# gatedelay_11-30-19.net
KiCad netlist of a schematic drawn in EAGLE
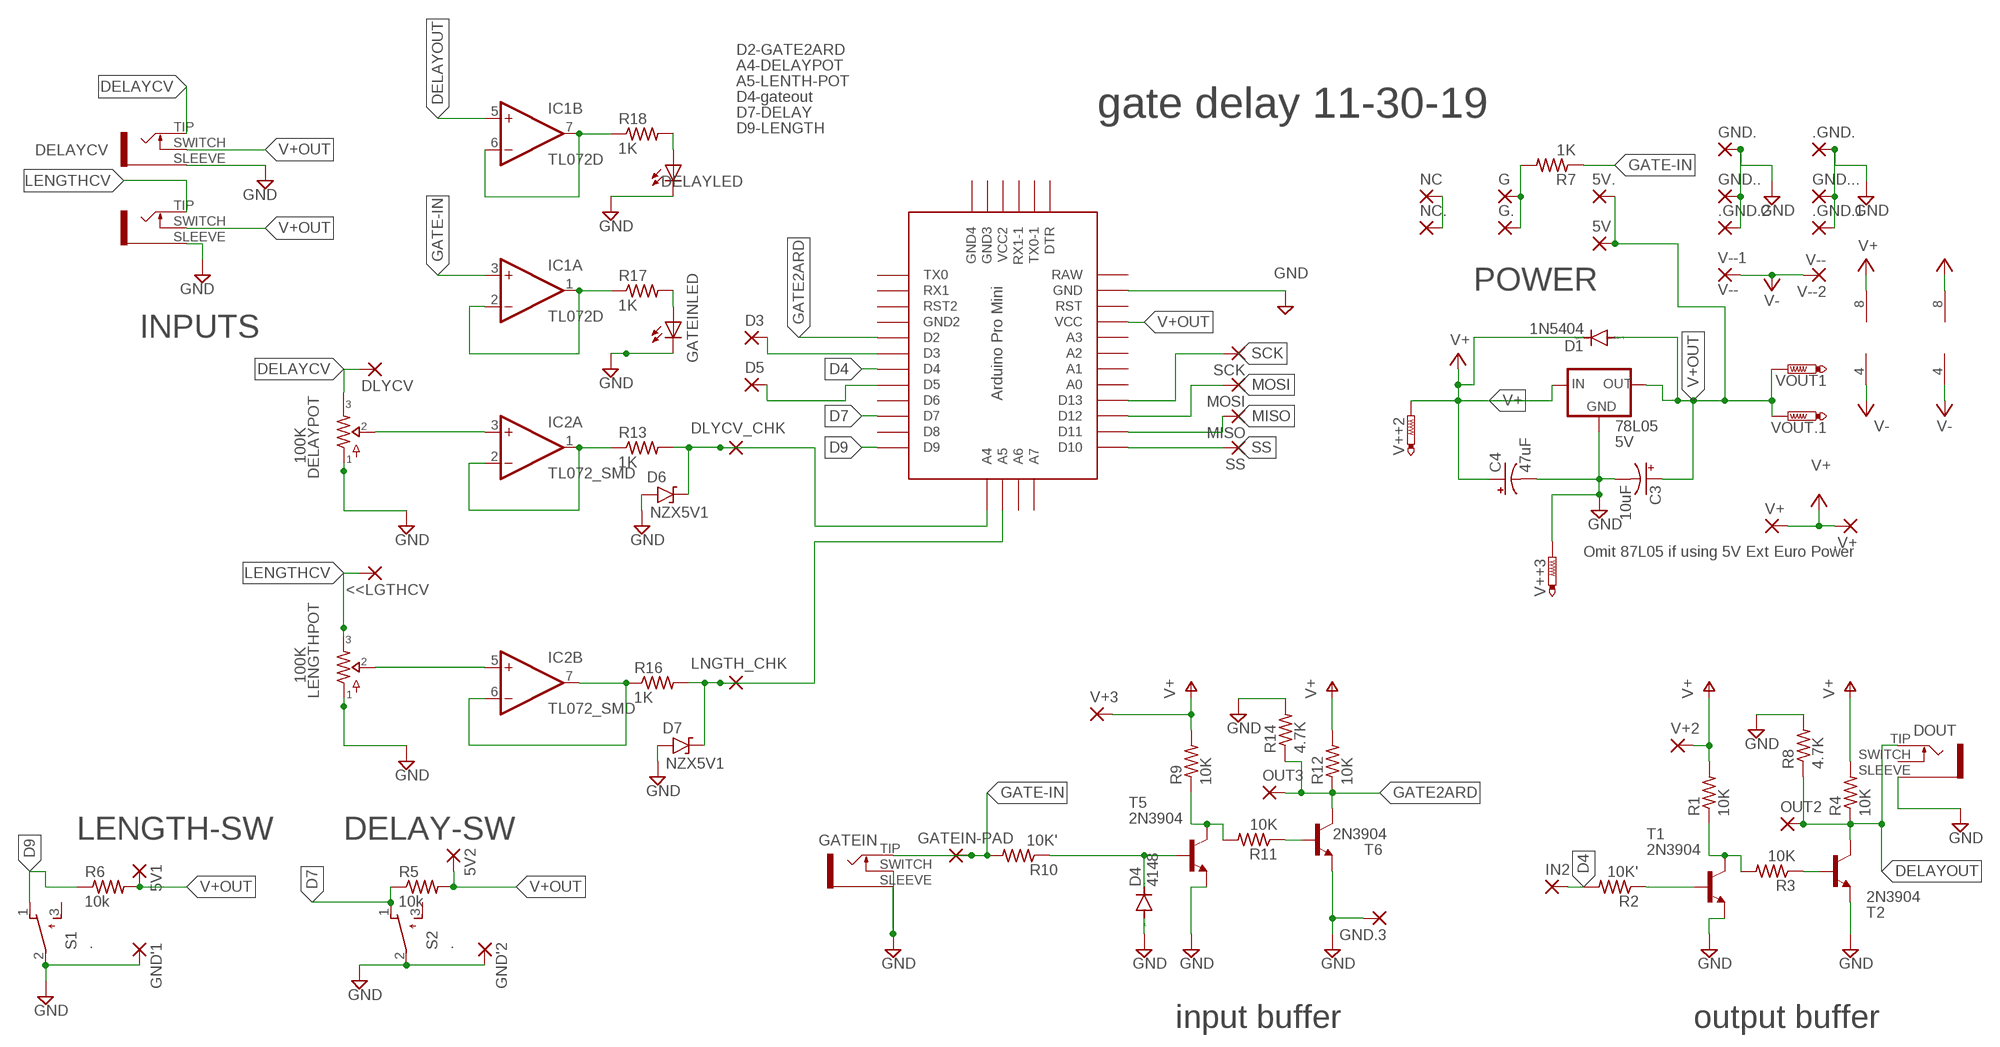
[diagram p0: schematic, sheet 1]

(export (version "E")
  (design (tool "Eeschema 10.0.6"))
  (components
    (comp (ref ".GND.")
      (value "1,6/0,8")
      (footprint "eagle-import:1,6_0,8")
      (libsource (lib "eagle-import") (part "1,6/0,8"))
    )
    (comp (ref ".GND.1")
      (value "1,6/0,8")
      (footprint "eagle-import:1,6_0,8")
      (libsource (lib "eagle-import") (part "1,6/0,8"))
    )
    (comp (ref ".GND.2")
      (value "1,6/0,8")
      (footprint "eagle-import:1,6_0,8")
      (libsource (lib "eagle-import") (part "1,6/0,8"))
    )
    (comp (ref ".V+")
      (value "1,6/0,8")
      (footprint "eagle-import:1,6_0,8")
      (libsource (lib "eagle-import") (part "1,6/0,8"))
    )
    (comp (ref "5V")
      (value "1,6/0,8")
      (footprint "eagle-import:1,6_0,8")
      (libsource (lib "eagle-import") (part "1,6/0,8"))
    )
    (comp (ref "5V.")
      (value "1,6/0,8")
      (footprint "eagle-import:1,6_0,8")
      (libsource (lib "eagle-import") (part "1,6/0,8"))
    )
    (comp (ref "5V1")
      (value "WIREPAD2,54/0,9")
      (footprint "eagle-import:2,54_0,9")
      (libsource (lib "eagle-import") (part "wirepad_412_WIREPAD2,54/0,9"))
    )
    (comp (ref "5V2")
      (value "WIREPAD2,54/0,9")
      (footprint "eagle-import:2,54_0,9")
      (libsource (lib "eagle-import") (part "wirepad_412_WIREPAD2,54/0,9"))
    )
    (comp (ref "78L05")
      (value "5V")
      (footprint "eagle-import:78LXX")
      (libsource (lib "eagle-import") (part "78LXX"))
    )
    (comp (ref "<<LGTHCV")
      (value "3,17/1,3")
      (footprint "eagle-import:3,17_1,3")
      (libsource (lib "eagle-import") (part "3,17/1,3"))
    )
    (comp (ref "C3")
      (value "10uF")
      (footprint "eagle-import:E2,5-6")
      (libsource (lib "eagle-import") (part "CPOL-USE2.5-6"))
    )
    (comp (ref "C4")
      (value "47uF")
      (footprint "eagle-import:E2,5-7")
      (libsource (lib "eagle-import") (part "CPOL-USE2.5-7"))
    )
    (comp (ref "D1")
      (value "1N5404")
      (footprint "eagle-import:DO35-10")
      (libsource (lib "eagle-import") (part "1N4148DO35-10"))
    )
    (comp (ref "D3")
      (value "WIREPAD2,15/1,0")
      (footprint "eagle-import:2,15_1,0")
      (libsource (lib "eagle-import") (part "wirepad_412_WIREPAD2,15/1,0"))
    )
    (comp (ref "D4")
      (value "4148")
      (footprint "eagle-import:DO35-7")
      (libsource (lib "eagle-import") (part "1N4148DO35-7"))
    )
    (comp (ref "D5")
      (value "WIREPAD2,15/1,0")
      (footprint "eagle-import:2,15_1,0")
      (libsource (lib "eagle-import") (part "wirepad_412_WIREPAD2,15/1,0"))
    )
    (comp (ref "D6")
      (value "NZX5V1")
      (footprint "eagle-import:DO41-2")
      (libsource (lib "eagle-import") (part "ZENER.2"))
    )
    (comp (ref "D7")
      (value "NZX5V1")
      (footprint "eagle-import:DO41-2")
      (libsource (lib "eagle-import") (part "ZENER.2"))
    )
    (comp (ref "DELAYCV")
      (value "35RAPC2AV")
      (footprint "eagle-import:35RAPCVAV")
      (libsource (lib "eagle-import") (part "35RAPC2AV"))
    )
    (comp (ref "DELAYLED")
      (value "LED3MM")
      (footprint "eagle-import:LED3MM")
      (libsource (lib "eagle-import") (part "LED3MM"))
    )
    (comp (ref "DELAYPOT")
      (value "100K")
      (footprint "eagle-import:9MM_VERT")
      (libsource (lib "eagle-import") (part "POTS9MM_VERT"))
    )
    (comp (ref "DLYCV")
      (value "WIREPAD1,6/0,9")
      (footprint "eagle-import:1,6_0,9")
      (libsource (lib "eagle-import") (part "WIREPAD1,6/0,9"))
    )
    (comp (ref "DLYCV_CHK")
      (value "3,17/1,3")
      (footprint "eagle-import:3,17_1,3")
      (libsource (lib "eagle-import") (part "3,17/1,3"))
    )
    (comp (ref "DOUT")
      (value "35RAPC2AV")
      (footprint "eagle-import:35RAPCVAV")
      (libsource (lib "eagle-import") (part "35RAPC2AV"))
    )
    (comp (ref "G")
      (value "1,6/0,8")
      (footprint "eagle-import:1,6_0,8")
      (libsource (lib "eagle-import") (part "1,6/0,8"))
    )
    (comp (ref "G.")
      (value "1,6/0,8")
      (footprint "eagle-import:1,6_0,8")
      (libsource (lib "eagle-import") (part "1,6/0,8"))
    )
    (comp (ref "GATEIN")
      (value "35RAPC2AV")
      (footprint "eagle-import:35RAPCVAV")
      (libsource (lib "eagle-import") (part "35RAPC2AV"))
    )
    (comp (ref "GATEIN-PAD")
      (value "WIREPAD1,6/0,9")
      (footprint "eagle-import:1,6_0,9")
      (libsource (lib "eagle-import") (part "WIREPAD1,6/0,9"))
    )
    (comp (ref "GATEINLED")
      (value "LED3MM")
      (footprint "eagle-import:LED3MM")
      (libsource (lib "eagle-import") (part "LED3MM"))
    )
    (comp (ref "GND'1")
      (value "WIREPAD2,54/0,9")
      (footprint "eagle-import:2,54_0,9")
      (libsource (lib "eagle-import") (part "wirepad_412_WIREPAD2,54/0,9"))
    )
    (comp (ref "GND'2")
      (value "WIREPAD2,54/0,9")
      (footprint "eagle-import:2,54_0,9")
      (libsource (lib "eagle-import") (part "wirepad_412_WIREPAD2,54/0,9"))
    )
    (comp (ref "GND.")
      (value "1,6/0,8")
      (footprint "eagle-import:1,6_0,8")
      (libsource (lib "eagle-import") (part "1,6/0,8"))
    )
    (comp (ref "GND..")
      (value "1,6/0,8")
      (footprint "eagle-import:1,6_0,8")
      (libsource (lib "eagle-import") (part "1,6/0,8"))
    )
    (comp (ref "GND...")
      (value "1,6/0,8")
      (footprint "eagle-import:1,6_0,8")
      (libsource (lib "eagle-import") (part "1,6/0,8"))
    )
    (comp (ref "GND.3")
      (value "WIREPAD1,6/0,9")
      (footprint "eagle-import:1,6_0,9")
      (libsource (lib "eagle-import") (part "WIREPAD1,6/0,9"))
    )
    (comp (ref "IC1")
      (value "TL072D")
      (footprint "eagle-import:SO08")
      (libsource (lib "eagle-import") (part "TL072D"))
    )
    (comp (ref "IC2")
      (value "TL072_SMD")
      (footprint "eagle-import:SO08")
      (libsource (lib "eagle-import") (part "TL072_SMD"))
    )
    (comp (ref "IN2")
      (value "WIREPAD1,6/0,9")
      (footprint "eagle-import:1,6_0,9")
      (libsource (lib "eagle-import") (part "WIREPAD1,6/0,9"))
    )
    (comp (ref "LENGTHCV")
      (value "35RAPC2AV")
      (footprint "eagle-import:35RAPCVAV")
      (libsource (lib "eagle-import") (part "35RAPC2AV"))
    )
    (comp (ref "LENGTHPOT")
      (value "100K")
      (footprint "eagle-import:9MM_VERT")
      (libsource (lib "eagle-import") (part "POTS9MM_VERT"))
    )
    (comp (ref "LNGTH_CHK")
      (value "3,17/1,3")
      (footprint "eagle-import:3,17_1,3")
      (libsource (lib "eagle-import") (part "3,17/1,3"))
    )
    (comp (ref "MISO")
      (value "WIREPAD1,6/0,9")
      (footprint "eagle-import:1,6_0,9")
      (libsource (lib "eagle-import") (part "WIREPAD1,6/0,9"))
    )
    (comp (ref "MOSI")
      (value "WIREPAD1,6/0,9")
      (footprint "eagle-import:1,6_0,9")
      (libsource (lib "eagle-import") (part "WIREPAD1,6/0,9"))
    )
    (comp (ref "NC")
      (value "1,6/0,8")
      (footprint "eagle-import:1,6_0,8")
      (libsource (lib "eagle-import") (part "1,6/0,8"))
    )
    (comp (ref "NC.")
      (value "1,6/0,8")
      (footprint "eagle-import:1,6_0,8")
      (libsource (lib "eagle-import") (part "1,6/0,8"))
    )
    (comp (ref "OUT2")
      (value "WIREPAD1,6/0,9")
      (footprint "eagle-import:1,6_0,9")
      (libsource (lib "eagle-import") (part "WIREPAD1,6/0,9"))
    )
    (comp (ref "OUT3")
      (value "WIREPAD1,6/0,9")
      (footprint "eagle-import:1,6_0,9")
      (libsource (lib "eagle-import") (part "WIREPAD1,6/0,9"))
    )
    (comp (ref "R1")
      (value "10K")
      (footprint "eagle-import:0204_5")
      (libsource (lib "eagle-import") (part "rcl_334_R-US_0204/5"))
    )
    (comp (ref "R2")
      (value "10K'")
      (footprint "eagle-import:0204_5")
      (libsource (lib "eagle-import") (part "rcl_334_R-US_0204/5"))
    )
    (comp (ref "R3")
      (value "10K")
      (footprint "eagle-import:0204_5")
      (libsource (lib "eagle-import") (part "rcl_334_R-US_0204/5"))
    )
    (comp (ref "R4")
      (value "10K")
      (footprint "eagle-import:0204_5")
      (libsource (lib "eagle-import") (part "rcl_334_R-US_0204/5"))
    )
    (comp (ref "R5")
      (value "10k")
      (footprint "eagle-import:0207_10")
      (libsource (lib "eagle-import") (part "R-US_0207/10"))
    )
    (comp (ref "R6")
      (value "10k")
      (footprint "eagle-import:0204_5")
      (libsource (lib "eagle-import") (part "R-US_0204/5"))
    )
    (comp (ref "R7")
      (value "1K")
      (footprint "eagle-import:0207_7")
      (libsource (lib "eagle-import") (part "R-US_0207/7"))
    )
    (comp (ref "R8")
      (value "4.7K")
      (footprint "eagle-import:0204_5")
      (libsource (lib "eagle-import") (part "rcl_334_R-US_0204/5"))
    )
    (comp (ref "R9")
      (value "10K")
      (footprint "eagle-import:0204_5")
      (libsource (lib "eagle-import") (part "rcl_334_R-US_0204/5"))
    )
    (comp (ref "R10")
      (value "10K'")
      (footprint "eagle-import:0204_5")
      (libsource (lib "eagle-import") (part "rcl_334_R-US_0204/5"))
    )
    (comp (ref "R11")
      (value "10K")
      (footprint "eagle-import:0204_5")
      (libsource (lib "eagle-import") (part "rcl_334_R-US_0204/5"))
    )
    (comp (ref "R12")
      (value "10K")
      (footprint "eagle-import:0204_5")
      (libsource (lib "eagle-import") (part "rcl_334_R-US_0204/5"))
    )
    (comp (ref "R13")
      (value "1K")
      (footprint "eagle-import:0204_7")
      (libsource (lib "eagle-import") (part "rcl_R-US_0204/7"))
    )
    (comp (ref "R14")
      (value "4.7K")
      (footprint "eagle-import:0204_5")
      (libsource (lib "eagle-import") (part "rcl_334_R-US_0204/5"))
    )
    (comp (ref "R16")
      (value "1K")
      (footprint "eagle-import:0204_7")
      (libsource (lib "eagle-import") (part "rcl_R-US_0204/7"))
    )
    (comp (ref "R17")
      (value "1K")
      (footprint "eagle-import:0204_7")
      (libsource (lib "eagle-import") (part "R-US_0204/7"))
    )
    (comp (ref "R18")
      (value "1K")
      (footprint "eagle-import:0207_15")
      (libsource (lib "eagle-import") (part "rcl_334_R-US_0207/15"))
    )
    (comp (ref "S1")
      (value ".")
      (footprint "eagle-import:ALCOSWTT11")
      (libsource (lib "eagle-import") (part "ALCOSWTT11"))
    )
    (comp (ref "S2")
      (value ".")
      (footprint "eagle-import:ALCOSWTT11")
      (libsource (lib "eagle-import") (part "ALCOSWTT11"))
    )
    (comp (ref "SCK")
      (value "WIREPAD1,6/0,9")
      (footprint "eagle-import:1,6_0,9")
      (libsource (lib "eagle-import") (part "WIREPAD1,6/0,9"))
    )
    (comp (ref "SS")
      (value "WIREPAD1,6/0,9")
      (footprint "eagle-import:1,6_0,9")
      (libsource (lib "eagle-import") (part "WIREPAD1,6/0,9"))
    )
    (comp (ref "T1")
      (value "2N3904")
      (footprint "eagle-import:TO92")
      (libsource (lib "eagle-import") (part "2N3904"))
    )
    (comp (ref "T2")
      (value "2N3904")
      (footprint "eagle-import:TO92")
      (libsource (lib "eagle-import") (part "2N3904"))
    )
    (comp (ref "T5")
      (value "2N3904")
      (footprint "eagle-import:TO92")
      (libsource (lib "eagle-import") (part "2N3904"))
    )
    (comp (ref "T6")
      (value "2N3904")
      (footprint "eagle-import:TO92")
      (libsource (lib "eagle-import") (part "2N3904"))
    )
    (comp (ref "U$1")
      (value "PRO-MINI")
      (footprint "eagle-import:PRO-MINI")
      (libsource (lib "eagle-import") (part "PRO-MINI"))
    )
    (comp (ref "V+")
      (value "1,6/0,8")
      (footprint "eagle-import:1,6_0,8")
      (libsource (lib "eagle-import") (part "1,6/0,8"))
    )
    (comp (ref "V++2")
      (value "PTR1PAD1-13Y")
      (footprint "eagle-import:P1-13Y")
      (libsource (lib "eagle-import") (part "PTR1PAD1-13Y"))
    )
    (comp (ref "V++3")
      (value "PTR1PAD1-13Y")
      (footprint "eagle-import:P1-13Y")
      (libsource (lib "eagle-import") (part "PTR1PAD1-13Y"))
    )
    (comp (ref "V+2")
      (value "WIREPAD1,6/0,9")
      (footprint "eagle-import:1,6_0,9")
      (libsource (lib "eagle-import") (part "WIREPAD1,6/0,9"))
    )
    (comp (ref "V+3")
      (value "WIREPAD1,6/0,9")
      (footprint "eagle-import:1,6_0,9")
      (libsource (lib "eagle-import") (part "WIREPAD1,6/0,9"))
    )
    (comp (ref "V--1")
      (value "V--")
      (footprint "eagle-import:1,6_0,8")
      (libsource (lib "eagle-import") (part "1,6/0,8"))
    )
    (comp (ref "V--2")
      (value "V--")
      (footprint "eagle-import:1,6_0,8")
      (libsource (lib "eagle-import") (part "1,6/0,8"))
    )
    (comp (ref "VOUT.1")
      (value "PTR1PAD1-13Y")
      (footprint "eagle-import:P1-13Y")
      (libsource (lib "eagle-import") (part "PTR1PAD1-13Y"))
    )
    (comp (ref "VOUT1")
      (value "PTR1PAD1-13Y")
      (footprint "eagle-import:P1-13Y")
      (libsource (lib "eagle-import") (part "PTR1PAD1-13Y"))
    )
  )
  (nets
    (net (code "1") (name "/RAW") (class "Default")
      (node (ref "U$1") (pin "RAW") (pinfunction "RAW_RAW") (pintype "power_in"))
    )
    (net (code "2") (name "D4") (class "Default")
      (node (ref "IN2") (pin "1") (pinfunction "P_1") (pintype "passive"))
      (node (ref "R2") (pin "2") (pinfunction "2_2") (pintype "passive"))
      (node (ref "U$1") (pin "D4") (pinfunction "D4_D4") (pintype "bidirectional"))
    )
    (net (code "3") (name "D7") (class "Default")
      (node (ref "R5") (pin "1") (pinfunction "1_1") (pintype "passive"))
      (node (ref "S2") (pin "1") (pinfunction "O_1") (pintype "passive"))
      (node (ref "U$1") (pin "D7") (pinfunction "D7_D7") (pintype "bidirectional"))
    )
    (net (code "4") (name "D9") (class "Default")
      (node (ref "R6") (pin "1") (pinfunction "1_1") (pintype "passive"))
      (node (ref "S1") (pin "1") (pinfunction "O_1") (pintype "passive"))
      (node (ref "U$1") (pin "D9") (pinfunction "D9_D9") (pintype "bidirectional"))
    )
    (net (code "5") (name "DELAYCV") (class "Default")
      (node (ref "DELAYCV") (pin "TIP") (pinfunction "2_TIP") (pintype "passive"))
      (node (ref "DELAYPOT") (pin "3") (pinfunction "3_3") (pintype "passive"))
      (node (ref "DLYCV") (pin "1") (pinfunction "P_1") (pintype "passive"))
    )
    (net (code "6") (name "DELAYOUT") (class "Default")
      (node (ref "DOUT") (pin "TIP") (pinfunction "2_TIP") (pintype "passive"))
      (node (ref "IC1") (pin "5") (pinfunction "+IN_5") (pintype "input"))
      (node (ref "OUT2") (pin "1") (pinfunction "P_1") (pintype "passive"))
      (node (ref "R4") (pin "1") (pinfunction "1_1") (pintype "passive"))
      (node (ref "R8") (pin "1") (pinfunction "1_1") (pintype "passive"))
      (node (ref "T2") (pin "1") (pinfunction "C_1") (pintype "passive"))
    )
    (net (code "7") (name "GATE-IN") (class "Default")
      (node (ref "GATEIN") (pin "TIP") (pinfunction "2_TIP") (pintype "passive"))
      (node (ref "GATEIN-PAD") (pin "1") (pinfunction "P_1") (pintype "passive"))
      (node (ref "IC1") (pin "3") (pinfunction "+IN_3") (pintype "input"))
      (node (ref "R10") (pin "2") (pinfunction "2_2") (pintype "passive"))
      (node (ref "R7") (pin "1") (pinfunction "1_1") (pintype "passive"))
    )
    (net (code "8") (name "GATE2ARD") (class "Default")
      (node (ref "OUT3") (pin "1") (pinfunction "P_1") (pintype "passive"))
      (node (ref "R12") (pin "1") (pinfunction "1_1") (pintype "passive"))
      (node (ref "R14") (pin "1") (pinfunction "1_1") (pintype "passive"))
      (node (ref "T6") (pin "1") (pinfunction "C_1") (pintype "passive"))
      (node (ref "U$1") (pin "D2") (pinfunction "D2_D2") (pintype "bidirectional"))
    )
    (net (code "9") (name "GND") (class "Default")
      (node (ref ".GND.") (pin "1") (pinfunction "P_1") (pintype "passive"))
      (node (ref ".GND.1") (pin "1") (pinfunction "P_1") (pintype "passive"))
      (node (ref ".GND.2") (pin "1") (pinfunction "P_1") (pintype "passive"))
      (node (ref "78L05") (pin "GND") (pinfunction "GND_GND") (pintype "input"))
      (node (ref "C3") (pin "-") (pinfunction "-_-") (pintype "passive"))
      (node (ref "C4") (pin "-") (pinfunction "-_-") (pintype "passive"))
      (node (ref "D4") (pin "A") (pinfunction "A_A") (pintype "passive"))
      (node (ref "D6") (pin "A") (pinfunction "A_A") (pintype "passive"))
      (node (ref "D7") (pin "A") (pinfunction "A_A") (pintype "passive"))
      (node (ref "DELAYCV") (pin "SLEEVE") (pinfunction "1_SLEEVE") (pintype "passive"))
      (node (ref "DELAYLED") (pin "K") (pinfunction "C_K") (pintype "passive"))
      (node (ref "DELAYPOT") (pin "1") (pinfunction "1_1") (pintype "passive"))
      (node (ref "DOUT") (pin "SLEEVE") (pinfunction "1_SLEEVE") (pintype "passive"))
      (node (ref "GATEIN") (pin "SLEEVE") (pinfunction "1_SLEEVE") (pintype "passive"))
      (node (ref "GATEIN") (pin "SWITCH") (pinfunction "3_SWITCH") (pintype "passive"))
      (node (ref "GATEINLED") (pin "K") (pinfunction "C_K") (pintype "passive"))
      (node (ref "GND'1") (pin "1") (pinfunction "P_1") (pintype "passive"))
      (node (ref "GND'2") (pin "1") (pinfunction "P_1") (pintype "passive"))
      (node (ref "GND.") (pin "1") (pinfunction "P_1") (pintype "passive"))
      (node (ref "GND..") (pin "1") (pinfunction "P_1") (pintype "passive"))
      (node (ref "GND...") (pin "1") (pinfunction "P_1") (pintype "passive"))
      (node (ref "GND.3") (pin "1") (pinfunction "P_1") (pintype "passive"))
      (node (ref "LENGTHCV") (pin "SLEEVE") (pinfunction "1_SLEEVE") (pintype "passive"))
      (node (ref "LENGTHPOT") (pin "1") (pinfunction "1_1") (pintype "passive"))
      (node (ref "R14") (pin "2") (pinfunction "2_2") (pintype "passive"))
      (node (ref "R8") (pin "2") (pinfunction "2_2") (pintype "passive"))
      (node (ref "S1") (pin "2") (pinfunction "P_2") (pintype "passive"))
      (node (ref "S2") (pin "2") (pinfunction "P_2") (pintype "passive"))
      (node (ref "T1") (pin "3") (pinfunction "E_3") (pintype "passive"))
      (node (ref "T2") (pin "3") (pinfunction "E_3") (pintype "passive"))
      (node (ref "T5") (pin "3") (pinfunction "E_3") (pintype "passive"))
      (node (ref "T6") (pin "3") (pinfunction "E_3") (pintype "passive"))
      (node (ref "U$1") (pin "GND") (pinfunction "GND_GND") (pintype "input"))
      (node (ref "V++3") (pin "TP") (pinfunction "TP_TP") (pintype "input"))
    )
    (net (code "10") (name "LENGTHCV") (class "Default")
      (node (ref "<<LGTHCV") (pin "1") (pinfunction "P_1") (pintype "passive"))
      (node (ref "LENGTHCV") (pin "TIP") (pinfunction "2_TIP") (pintype "passive"))
      (node (ref "LENGTHPOT") (pin "3") (pinfunction "3_3") (pintype "passive"))
    )
    (net (code "11") (name "MISO") (class "Default")
      (node (ref "MISO") (pin "1") (pinfunction "P_1") (pintype "passive"))
      (node (ref "U$1") (pin "D11") (pinfunction "D11_D11") (pintype "bidirectional"))
    )
    (net (code "12") (name "MOSI") (class "Default")
      (node (ref "MOSI") (pin "1") (pinfunction "P_1") (pintype "passive"))
      (node (ref "U$1") (pin "D12") (pinfunction "D12_D12") (pintype "bidirectional"))
    )
    (net (code "13") (name "Net-(D3-P)") (class "Default")
      (node (ref "D3") (pin "1") (pinfunction "P_1") (pintype "passive"))
      (node (ref "U$1") (pin "D3") (pinfunction "D3_D3") (pintype "bidirectional"))
    )
    (net (code "14") (name "Net-(D5-P)") (class "Default")
      (node (ref "D5") (pin "1") (pinfunction "P_1") (pintype "passive"))
      (node (ref "U$1") (pin "D5") (pinfunction "D5_D5") (pintype "bidirectional"))
    )
    (net (code "15") (name "Net-(DELAYLED-PadA)") (class "Default")
      (node (ref "DELAYLED") (pin "A") (pinfunction "A_A") (pintype "passive"))
      (node (ref "R18") (pin "2") (pinfunction "2_2") (pintype "passive"))
    )
    (net (code "16") (name "Net-(DLYCV_CHK-P)") (class "Default")
      (node (ref "D6") (pin "C") (pinfunction "C_C") (pintype "passive"))
      (node (ref "DLYCV_CHK") (pin "1") (pinfunction "P_1") (pintype "passive"))
      (node (ref "R13") (pin "2") (pinfunction "2_2") (pintype "passive"))
      (node (ref "U$1") (pin "A4") (pinfunction "A4_A4") (pintype "bidirectional"))
    )
    (net (code "17") (name "Net-(G-P)") (class "Default")
      (node (ref "G") (pin "1") (pinfunction "P_1") (pintype "passive"))
      (node (ref "G.") (pin "1") (pinfunction "P_1") (pintype "passive"))
      (node (ref "R7") (pin "2") (pinfunction "2_2") (pintype "passive"))
    )
    (net (code "18") (name "Net-(GATEINLED-PadA)") (class "Default")
      (node (ref "GATEINLED") (pin "A") (pinfunction "A_A") (pintype "passive"))
      (node (ref "R17") (pin "2") (pinfunction "2_2") (pintype "passive"))
    )
    (net (code "19") (name "Net-(IC1A--IN)") (class "Default")
      (node (ref "IC1") (pin "1") (pinfunction "OUT_1") (pintype "output"))
      (node (ref "IC1") (pin "2") (pinfunction "-IN_2") (pintype "input"))
      (node (ref "R17") (pin "1") (pinfunction "1_1") (pintype "passive"))
    )
    (net (code "20") (name "Net-(IC1B--IN)") (class "Default")
      (node (ref "IC1") (pin "6") (pinfunction "-IN_6") (pintype "input"))
      (node (ref "IC1") (pin "7") (pinfunction "OUT_7") (pintype "output"))
      (node (ref "R18") (pin "1") (pinfunction "1_1") (pintype "passive"))
    )
    (net (code "21") (name "Net-(IC2A-+IN)") (class "Default")
      (node (ref "DELAYPOT") (pin "2") (pinfunction "2_2") (pintype "passive"))
      (node (ref "IC2") (pin "3") (pinfunction "+IN_3") (pintype "input"))
    )
    (net (code "22") (name "Net-(IC2A--IN)") (class "Default")
      (node (ref "IC2") (pin "1") (pinfunction "OUT_1") (pintype "output"))
      (node (ref "IC2") (pin "2") (pinfunction "-IN_2") (pintype "input"))
      (node (ref "R13") (pin "1") (pinfunction "1_1") (pintype "passive"))
    )
    (net (code "23") (name "Net-(IC2B-+IN)") (class "Default")
      (node (ref "IC2") (pin "5") (pinfunction "+IN_5") (pintype "input"))
      (node (ref "LENGTHPOT") (pin "2") (pinfunction "2_2") (pintype "passive"))
    )
    (net (code "24") (name "Net-(IC2B--IN)") (class "Default")
      (node (ref "IC2") (pin "6") (pinfunction "-IN_6") (pintype "input"))
      (node (ref "IC2") (pin "7") (pinfunction "OUT_7") (pintype "output"))
      (node (ref "R16") (pin "1") (pinfunction "1_1") (pintype "passive"))
    )
    (net (code "25") (name "Net-(LNGTH_CHK-P)") (class "Default")
      (node (ref "D7") (pin "C") (pinfunction "C_C") (pintype "passive"))
      (node (ref "LNGTH_CHK") (pin "1") (pinfunction "P_1") (pintype "passive"))
      (node (ref "R16") (pin "2") (pinfunction "2_2") (pintype "passive"))
      (node (ref "U$1") (pin "A5") (pinfunction "A5_A5") (pintype "bidirectional"))
    )
    (net (code "26") (name "Net-(NC-P)") (class "Default")
      (node (ref "NC") (pin "1") (pinfunction "P_1") (pintype "passive"))
      (node (ref "NC.") (pin "1") (pinfunction "P_1") (pintype "passive"))
    )
    (net (code "27") (name "Net-(T1-B)") (class "Default")
      (node (ref "R2") (pin "1") (pinfunction "1_1") (pintype "passive"))
      (node (ref "T1") (pin "2") (pinfunction "B_2") (pintype "passive"))
    )
    (net (code "28") (name "Net-(T1-C)") (class "Default")
      (node (ref "R1") (pin "1") (pinfunction "1_1") (pintype "passive"))
      (node (ref "R3") (pin "2") (pinfunction "2_2") (pintype "passive"))
      (node (ref "T1") (pin "1") (pinfunction "C_1") (pintype "passive"))
    )
    (net (code "29") (name "Net-(T2-B)") (class "Default")
      (node (ref "R3") (pin "1") (pinfunction "1_1") (pintype "passive"))
      (node (ref "T2") (pin "2") (pinfunction "B_2") (pintype "passive"))
    )
    (net (code "30") (name "Net-(T5-B)") (class "Default")
      (node (ref "D4") (pin "C") (pinfunction "C_C") (pintype "passive"))
      (node (ref "R10") (pin "1") (pinfunction "1_1") (pintype "passive"))
      (node (ref "T5") (pin "2") (pinfunction "B_2") (pintype "passive"))
    )
    (net (code "31") (name "Net-(T5-C)") (class "Default")
      (node (ref "R11") (pin "2") (pinfunction "2_2") (pintype "passive"))
      (node (ref "R9") (pin "1") (pinfunction "1_1") (pintype "passive"))
      (node (ref "T5") (pin "1") (pinfunction "C_1") (pintype "passive"))
    )
    (net (code "32") (name "Net-(T6-B)") (class "Default")
      (node (ref "R11") (pin "1") (pinfunction "1_1") (pintype "passive"))
      (node (ref "T6") (pin "2") (pinfunction "B_2") (pintype "passive"))
    )
    (net (code "33") (name "SCK") (class "Default")
      (node (ref "SCK") (pin "1") (pinfunction "P_1") (pintype "passive"))
      (node (ref "U$1") (pin "D13") (pinfunction "D13_D13") (pintype "bidirectional"))
    )
    (net (code "34") (name "SS") (class "Default")
      (node (ref "SS") (pin "1") (pinfunction "P_1") (pintype "passive"))
      (node (ref "U$1") (pin "D10") (pinfunction "D10_D10") (pintype "bidirectional"))
    )
    (net (code "35") (name "V+") (class "Default")
      (node (ref ".V+") (pin "1") (pinfunction "P_1") (pintype "passive"))
      (node (ref "78L05") (pin "IN") (pinfunction "IN_IN") (pintype "input"))
      (node (ref "C4") (pin "+") (pinfunction "+_+") (pintype "passive"))
      (node (ref "D1") (pin "C") (pinfunction "C_C") (pintype "passive"))
      (node (ref "IC1") (pin "8") (pinfunction "V+_8") (pintype "power_in"))
      (node (ref "IC2") (pin "8") (pinfunction "V+_8") (pintype "power_in"))
      (node (ref "R1") (pin "2") (pinfunction "2_2") (pintype "passive"))
      (node (ref "R12") (pin "2") (pinfunction "2_2") (pintype "passive"))
      (node (ref "R4") (pin "2") (pinfunction "2_2") (pintype "passive"))
      (node (ref "R9") (pin "2") (pinfunction "2_2") (pintype "passive"))
      (node (ref "V+") (pin "1") (pinfunction "P_1") (pintype "passive"))
      (node (ref "V++2") (pin "TP") (pinfunction "TP_TP") (pintype "input"))
      (node (ref "V+2") (pin "1") (pinfunction "P_1") (pintype "passive"))
      (node (ref "V+3") (pin "1") (pinfunction "P_1") (pintype "passive"))
    )
    (net (code "36") (name "V+OUT") (class "Default")
      (node (ref "5V") (pin "1") (pinfunction "P_1") (pintype "passive"))
      (node (ref "5V.") (pin "1") (pinfunction "P_1") (pintype "passive"))
      (node (ref "5V1") (pin "1") (pinfunction "P_1") (pintype "passive"))
      (node (ref "5V2") (pin "1") (pinfunction "P_1") (pintype "passive"))
      (node (ref "78L05") (pin "OUT") (pinfunction "OUT_OUT") (pintype "passive"))
      (node (ref "C3") (pin "+") (pinfunction "+_+") (pintype "passive"))
      (node (ref "D1") (pin "A") (pinfunction "A_A") (pintype "passive"))
      (node (ref "DELAYCV") (pin "SWITCH") (pinfunction "3_SWITCH") (pintype "passive"))
      (node (ref "LENGTHCV") (pin "SWITCH") (pinfunction "3_SWITCH") (pintype "passive"))
      (node (ref "R5") (pin "2") (pinfunction "2_2") (pintype "passive"))
      (node (ref "R6") (pin "2") (pinfunction "2_2") (pintype "passive"))
      (node (ref "U$1") (pin "VCC") (pinfunction "VCC_VCC") (pintype "bidirectional"))
      (node (ref "VOUT.1") (pin "TP") (pinfunction "TP_TP") (pintype "input"))
      (node (ref "VOUT1") (pin "TP") (pinfunction "TP_TP") (pintype "input"))
    )
    (net (code "37") (name "V-") (class "Default")
      (node (ref "IC1") (pin "4") (pinfunction "V-_4") (pintype "power_in"))
      (node (ref "IC2") (pin "4") (pinfunction "V-_4") (pintype "power_in"))
      (node (ref "V--1") (pin "1") (pinfunction "P_1") (pintype "passive"))
      (node (ref "V--2") (pin "1") (pinfunction "P_1") (pintype "passive"))
    )
    (net (code "38") (name "unconnected-(DOUT-3-PadSWITCH)") (class "Default")
      (node (ref "DOUT") (pin "SWITCH") (pinfunction "3_SWITCH") (pintype "passive"))
    )
    (net (code "39") (name "unconnected-(S1-S-Pad3)") (class "Default")
      (node (ref "S1") (pin "3") (pinfunction "S_3") (pintype "passive"))
    )
    (net (code "40") (name "unconnected-(S2-S-Pad3)") (class "Default")
      (node (ref "S2") (pin "3") (pinfunction "S_3") (pintype "passive"))
    )
    (net (code "41") (name "unconnected-(U$1-GND2-PadGND1)") (class "Default")
      (node (ref "U$1") (pin "GND1") (pinfunction "GND2_GND1") (pintype "bidirectional"))
    )
    (net (code "42") (name "unconnected-(U$1-GND4-PadGND2)") (class "Default")
      (node (ref "U$1") (pin "GND2") (pinfunction "GND4_GND2") (pintype "bidirectional"))
    )
    (net (code "43") (name "unconnected-(U$1-PadA0)") (class "Default")
      (node (ref "U$1") (pin "A0") (pinfunction "A0_A0") (pintype "bidirectional"))
    )
    (net (code "44") (name "unconnected-(U$1-PadA1)") (class "Default")
      (node (ref "U$1") (pin "A1") (pinfunction "A1_A1") (pintype "bidirectional"))
    )
    (net (code "45") (name "unconnected-(U$1-PadA2)") (class "Default")
      (node (ref "U$1") (pin "A2") (pinfunction "A2_A2") (pintype "bidirectional"))
    )
    (net (code "46") (name "unconnected-(U$1-PadA3)") (class "Default")
      (node (ref "U$1") (pin "A3") (pinfunction "A3_A3") (pintype "bidirectional"))
    )
    (net (code "47") (name "unconnected-(U$1-PadA6)") (class "Default")
      (node (ref "U$1") (pin "A6") (pinfunction "A6_A6") (pintype "bidirectional"))
    )
    (net (code "48") (name "unconnected-(U$1-PadA7)") (class "Default")
      (node (ref "U$1") (pin "A7") (pinfunction "A7_A7") (pintype "bidirectional"))
    )
    (net (code "49") (name "unconnected-(U$1-PadD6)") (class "Default")
      (node (ref "U$1") (pin "D6") (pinfunction "D6_D6") (pintype "bidirectional"))
    )
    (net (code "50") (name "unconnected-(U$1-PadD8)") (class "Default")
      (node (ref "U$1") (pin "D8") (pinfunction "D8_D8") (pintype "bidirectional"))
    )
    (net (code "51") (name "unconnected-(U$1-PadDTR)") (class "Default")
      (node (ref "U$1") (pin "DTR") (pinfunction "DTR_DTR") (pintype "bidirectional"))
    )
    (net (code "52") (name "unconnected-(U$1-PadGND3)") (class "Default")
      (node (ref "U$1") (pin "GND3") (pinfunction "GND3_GND3") (pintype "bidirectional"))
    )
    (net (code "53") (name "unconnected-(U$1-PadRST)") (class "Default")
      (node (ref "U$1") (pin "RST") (pinfunction "RST_RST") (pintype "bidirectional"))
    )
    (net (code "54") (name "unconnected-(U$1-PadRX1)") (class "Default")
      (node (ref "U$1") (pin "RX1") (pinfunction "RX1_RX1") (pintype "bidirectional"))
    )
    (net (code "55") (name "unconnected-(U$1-PadRX1-1)") (class "Default")
      (node (ref "U$1") (pin "RX1-1") (pinfunction "RX1-1_RX1-1") (pintype "bidirectional"))
    )
    (net (code "56") (name "unconnected-(U$1-PadTX0)") (class "Default")
      (node (ref "U$1") (pin "TX0") (pinfunction "TX0_TX0") (pintype "bidirectional"))
    )
    (net (code "57") (name "unconnected-(U$1-PadTX0-1)") (class "Default")
      (node (ref "U$1") (pin "TX0-1") (pinfunction "TX0-1_TX0-1") (pintype "bidirectional"))
    )
    (net (code "58") (name "unconnected-(U$1-RST2-PadRST1)") (class "Default")
      (node (ref "U$1") (pin "RST1") (pinfunction "RST2_RST1") (pintype "bidirectional"))
    )
    (net (code "59") (name "unconnected-(U$1-VCC2-PadVCC1)") (class "Default")
      (node (ref "U$1") (pin "VCC1") (pinfunction "VCC2_VCC1") (pintype "bidirectional"))
    )
  )
)
